# OLED_Kij_SPI.net
KiCad netlist of a schematic drawn in EAGLE
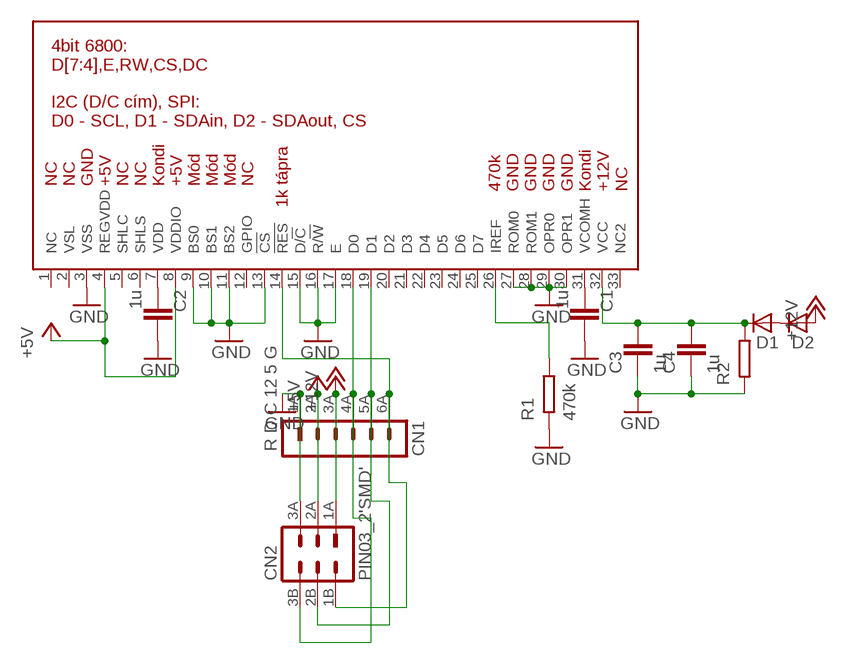
[diagram p0: schematic, sheet 1]

(export (version "E")
  (design (tool "Eeschema 10.0.6"))
  (components
    (comp (ref "C1")
      (value "1u")
      (footprint "eagle-import:R0805")
      (libsource (lib "eagle-import") (part "C0805"))
    )
    (comp (ref "C2")
      (value "1u")
      (footprint "eagle-import:R0805")
      (libsource (lib "eagle-import") (part "C0805"))
    )
    (comp (ref "C3")
      (value "1u")
      (footprint "eagle-import:R0805")
      (libsource (lib "eagle-import") (part "C0805"))
    )
    (comp (ref "C4")
      (value "1u")
      (footprint "eagle-import:R0805")
      (libsource (lib "eagle-import") (part "C0805"))
    )
    (comp (ref "CN1")
      (value "R D C 12 5 G")
      (footprint "eagle-import:PIN_HEADER_1X6")
      (libsource (lib "eagle-import") (part "PIN06_1SMD"))
    )
    (comp (ref "CN2")
      (value "PIN03_2'SMD'")
      (footprint "eagle-import:PIN_HEADER_2X3")
      (libsource (lib "eagle-import") (part "PIN03_2'SMD'"))
    )
    (comp (ref "D1")
      (value "D0805")
      (footprint "eagle-import:D0805")
      (libsource (lib "eagle-import") (part "D0805"))
    )
    (comp (ref "D2")
      (value "D0805")
      (footprint "eagle-import:D0805")
      (libsource (lib "eagle-import") (part "D0805"))
    )
    (comp (ref "R1")
      (value "470k")
      (footprint "eagle-import:R0805")
      (libsource (lib "eagle-import") (part "R_EU0805"))
    )
    (comp (ref "R2")
      (value "R_EU0805")
      (footprint "eagle-import:R0805")
      (libsource (lib "eagle-import") (part "R_EU0805"))
    )
    (comp (ref "U$1")
      (value "OLED_DISPL")
      (footprint "eagle-import:OLED_DISPL")
      (libsource (lib "eagle-import") (part "OLED_DISPL"))
    )
  )
  (nets
    (net (code "1") (name "+5V") (class "Default")
      (node (ref "CN1") (pin "2A") (pinfunction "2_2A") (pintype "passive"))
      (node (ref "CN2") (pin "2A") (pinfunction "3_2A") (pintype "passive"))
      (node (ref "U$1") (pin "4") (pinfunction "REGVDD_4") (pintype "bidirectional"))
      (node (ref "U$1") (pin "8") (pinfunction "VDDIO_8") (pintype "bidirectional"))
    )
    (net (code "2") (name "+12V") (class "Default")
      (node (ref "CN1") (pin "3A") (pinfunction "3_3A") (pintype "passive"))
      (node (ref "CN2") (pin "1A") (pinfunction "1_1A") (pintype "passive"))
      (node (ref "D2") (pin "1") (pinfunction "A_1") (pintype "passive"))
    )
    (net (code "3") (name "GND") (class "Default")
      (node (ref "C1") (pin "1") (pinfunction "1_1") (pintype "passive"))
      (node (ref "C2") (pin "1") (pinfunction "1_1") (pintype "passive"))
      (node (ref "C3") (pin "2") (pinfunction "2_2") (pintype "passive"))
      (node (ref "C4") (pin "2") (pinfunction "2_2") (pintype "passive"))
      (node (ref "CN1") (pin "1A") (pinfunction "1_1A") (pintype "passive"))
      (node (ref "CN2") (pin "3A") (pinfunction "5_3A") (pintype "passive"))
      (node (ref "R1") (pin "1") (pinfunction "A_1") (pintype "passive"))
      (node (ref "R2") (pin "1") (pinfunction "A_1") (pintype "passive"))
      (node (ref "U$1") (pin "10") (pinfunction "BS1_10") (pintype "bidirectional"))
      (node (ref "U$1") (pin "11") (pinfunction "BS2_11") (pintype "bidirectional"))
      (node (ref "U$1") (pin "13") (pinfunction "~{CS}_13") (pintype "bidirectional"))
      (node (ref "U$1") (pin "15") (pinfunction "D/~{C}_15") (pintype "bidirectional"))
      (node (ref "U$1") (pin "16") (pinfunction "R/~{W}_16") (pintype "bidirectional"))
      (node (ref "U$1") (pin "17") (pinfunction "E_17") (pintype "bidirectional"))
      (node (ref "U$1") (pin "27") (pinfunction "ROM0_27") (pintype "bidirectional"))
      (node (ref "U$1") (pin "28") (pinfunction "ROM1_28") (pintype "bidirectional"))
      (node (ref "U$1") (pin "29") (pinfunction "OPR0_29") (pintype "bidirectional"))
      (node (ref "U$1") (pin "3") (pinfunction "VSS_3") (pintype "bidirectional"))
      (node (ref "U$1") (pin "30") (pinfunction "OPR1_30") (pintype "bidirectional"))
      (node (ref "U$1") (pin "9") (pinfunction "BS0_9") (pintype "bidirectional"))
    )
    (net (code "4") (name "Net-(CN1-4)") (class "Default")
      (node (ref "CN1") (pin "4A") (pinfunction "4_4A") (pintype "passive"))
      (node (ref "CN2") (pin "3B") (pinfunction "6_3B") (pintype "passive"))
      (node (ref "U$1") (pin "18") (pinfunction "D0_18") (pintype "bidirectional"))
    )
    (net (code "5") (name "Net-(CN1-5)") (class "Default")
      (node (ref "CN1") (pin "5A") (pinfunction "5_5A") (pintype "passive"))
      (node (ref "CN2") (pin "2B") (pinfunction "4_2B") (pintype "passive"))
      (node (ref "U$1") (pin "19") (pinfunction "D1_19") (pintype "bidirectional"))
    )
    (net (code "6") (name "Net-(CN1-6)") (class "Default")
      (node (ref "CN1") (pin "6A") (pinfunction "6_6A") (pintype "passive"))
      (node (ref "CN2") (pin "1B") (pinfunction "2_1B") (pintype "passive"))
      (node (ref "U$1") (pin "14") (pinfunction "~{RES}_14") (pintype "bidirectional"))
    )
    (net (code "7") (name "Net-(D1-A)") (class "Default")
      (node (ref "D1") (pin "1") (pinfunction "A_1") (pintype "passive"))
      (node (ref "D2") (pin "2") (pinfunction "C_2") (pintype "passive"))
    )
    (net (code "8") (name "Net-(D1-C)") (class "Default")
      (node (ref "C3") (pin "1") (pinfunction "1_1") (pintype "passive"))
      (node (ref "C4") (pin "1") (pinfunction "1_1") (pintype "passive"))
      (node (ref "D1") (pin "2") (pinfunction "C_2") (pintype "passive"))
      (node (ref "R2") (pin "2") (pinfunction "E_2") (pintype "passive"))
      (node (ref "U$1") (pin "32") (pinfunction "VCC_32") (pintype "bidirectional"))
    )
    (net (code "9") (name "Net-(R1-E)") (class "Default")
      (node (ref "R1") (pin "2") (pinfunction "E_2") (pintype "passive"))
      (node (ref "U$1") (pin "26") (pinfunction "IREF_26") (pintype "bidirectional"))
    )
    (net (code "10") (name "Net-(U$1-VCOMH)") (class "Default")
      (node (ref "C1") (pin "2") (pinfunction "2_2") (pintype "passive"))
      (node (ref "U$1") (pin "31") (pinfunction "VCOMH_31") (pintype "bidirectional"))
    )
    (net (code "11") (name "Net-(U$1-VDD)") (class "Default")
      (node (ref "C2") (pin "2") (pinfunction "2_2") (pintype "passive"))
      (node (ref "U$1") (pin "7") (pinfunction "VDD_7") (pintype "bidirectional"))
    )
    (net (code "12") (name "unconnected-(U$1-D2-Pad20)") (class "Default")
      (node (ref "U$1") (pin "20") (pinfunction "D2_20") (pintype "bidirectional"))
    )
    (net (code "13") (name "unconnected-(U$1-D3-Pad21)") (class "Default")
      (node (ref "U$1") (pin "21") (pinfunction "D3_21") (pintype "bidirectional"))
    )
    (net (code "14") (name "unconnected-(U$1-D4-Pad22)") (class "Default")
      (node (ref "U$1") (pin "22") (pinfunction "D4_22") (pintype "bidirectional"))
    )
    (net (code "15") (name "unconnected-(U$1-D5-Pad23)") (class "Default")
      (node (ref "U$1") (pin "23") (pinfunction "D5_23") (pintype "bidirectional"))
    )
    (net (code "16") (name "unconnected-(U$1-D6-Pad24)") (class "Default")
      (node (ref "U$1") (pin "24") (pinfunction "D6_24") (pintype "bidirectional"))
    )
    (net (code "17") (name "unconnected-(U$1-D7-Pad25)") (class "Default")
      (node (ref "U$1") (pin "25") (pinfunction "D7_25") (pintype "bidirectional"))
    )
    (net (code "18") (name "unconnected-(U$1-GPIO-Pad12)") (class "Default")
      (node (ref "U$1") (pin "12") (pinfunction "GPIO_12") (pintype "bidirectional"))
    )
    (net (code "19") (name "unconnected-(U$1-NC-Pad1)") (class "Default")
      (node (ref "U$1") (pin "1") (pinfunction "NC_1") (pintype "bidirectional"))
    )
    (net (code "20") (name "unconnected-(U$1-NC2-Pad33)") (class "Default")
      (node (ref "U$1") (pin "33") (pinfunction "NC2_33") (pintype "bidirectional"))
    )
    (net (code "21") (name "unconnected-(U$1-SHLC-Pad5)") (class "Default")
      (node (ref "U$1") (pin "5") (pinfunction "SHLC_5") (pintype "bidirectional"))
    )
    (net (code "22") (name "unconnected-(U$1-SHLS-Pad6)") (class "Default")
      (node (ref "U$1") (pin "6") (pinfunction "SHLS_6") (pintype "bidirectional"))
    )
    (net (code "23") (name "unconnected-(U$1-VSL-Pad2)") (class "Default")
      (node (ref "U$1") (pin "2") (pinfunction "VSL_2") (pintype "bidirectional"))
    )
  )
)
